# SparkFun_MOSFET_Power_Control_Kit.net
KiCad netlist of a schematic drawn in EAGLE
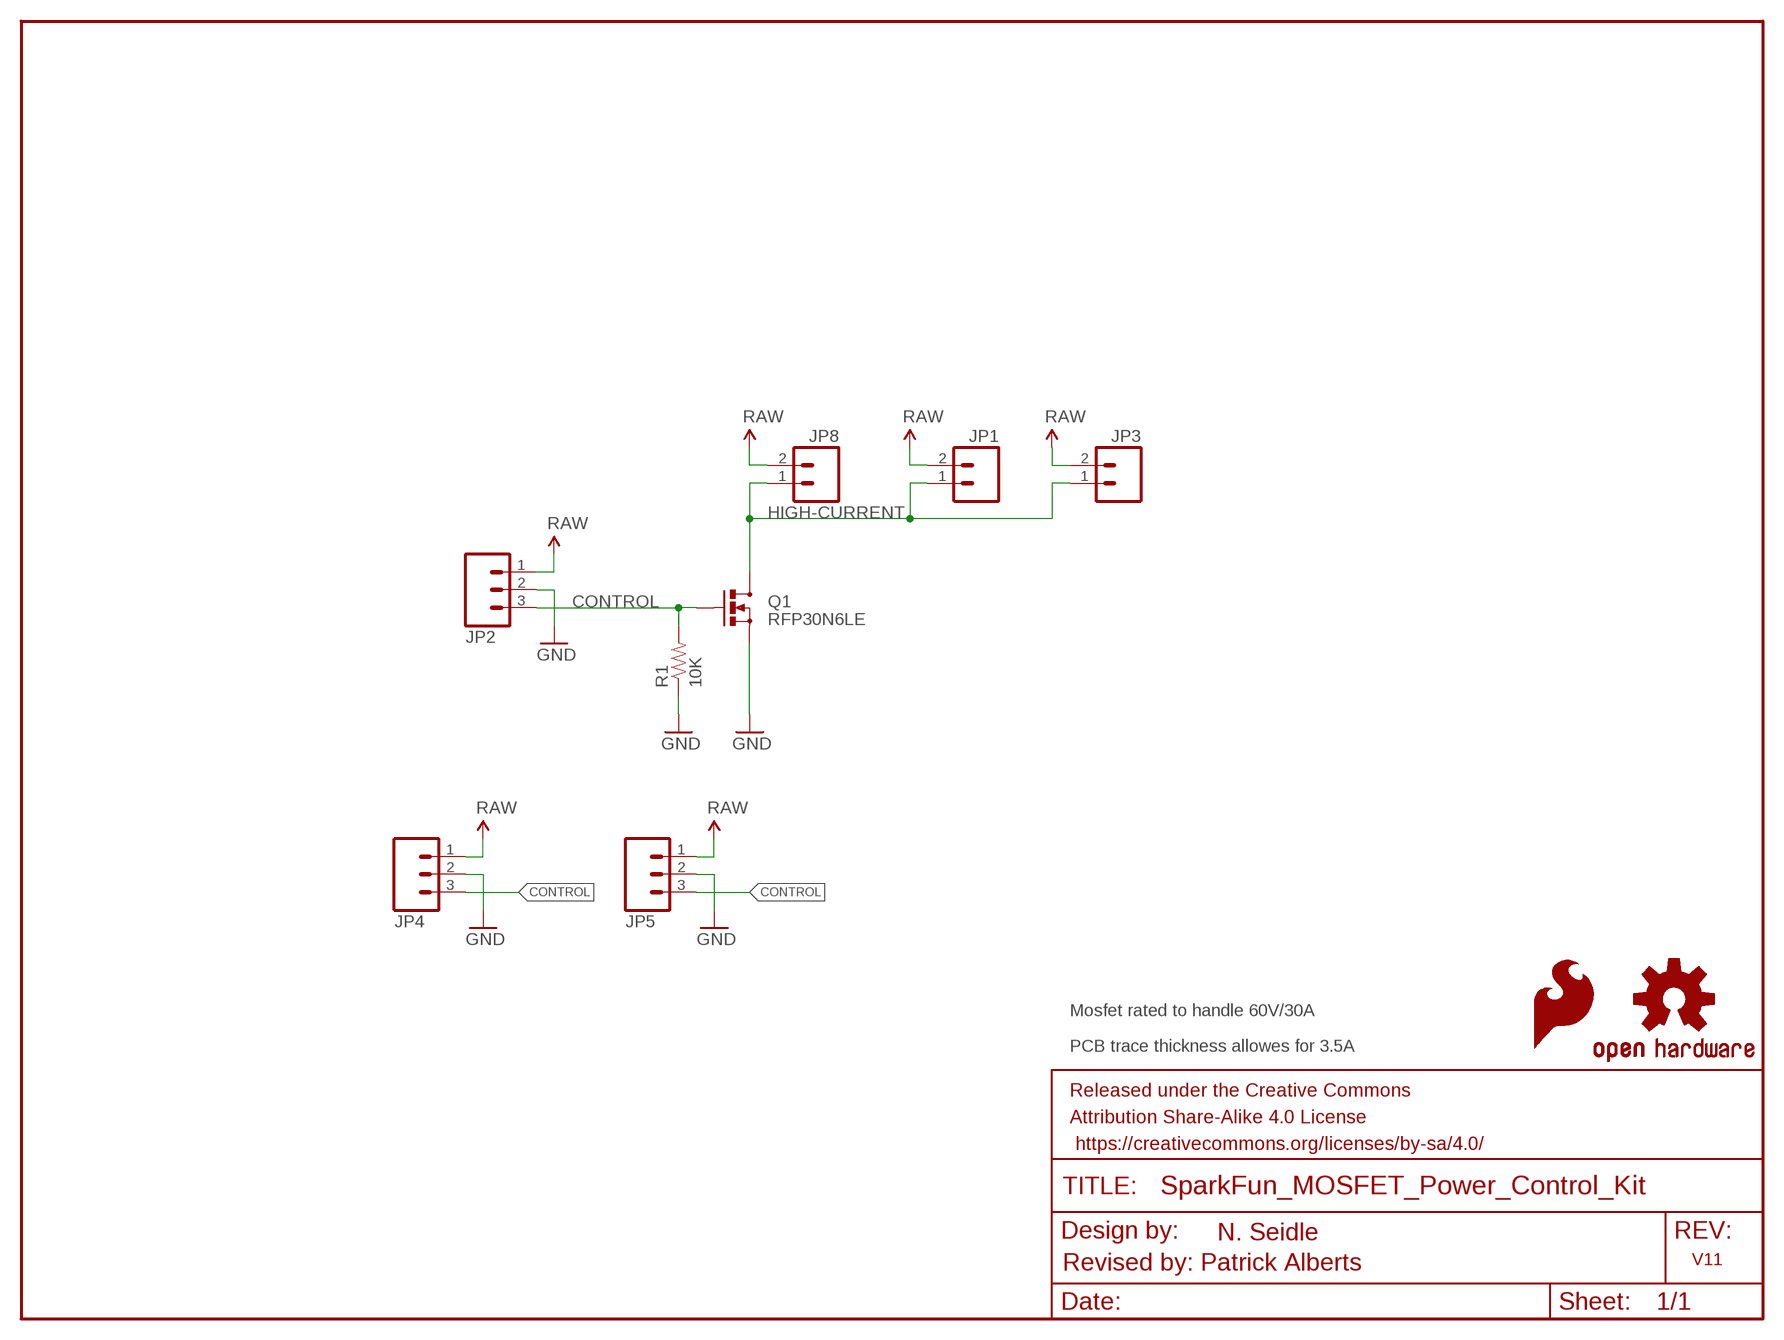
[diagram p0: schematic, sheet 1]

(export (version "E")
  (design (tool "Eeschema 10.0.6"))
  (components
    (comp (ref "FRAME1")
      (value "FRAME-LETTER")
      (footprint "eagle-import:CREATIVE_COMMONS")
      (libsource (lib "eagle-import") (part "FRAME-LETTER"))
    )
    (comp (ref "JP1")
      (value "M023.5MM")
      (footprint "eagle-import:SCREWTERMINAL-3.5MM-2")
      (libsource (lib "eagle-import") (part "M023.5MM"))
    )
    (comp (ref "JP2")
      (value "M03JST-PTH")
      (footprint "eagle-import:JST-3-PTH")
      (libsource (lib "eagle-import") (part "M03JST-PTH"))
    )
    (comp (ref "JP3")
      (value "M02PTH")
      (footprint "eagle-import:1X02")
      (libsource (lib "eagle-import") (part "SparkFun-Connectors_M02PTH"))
    )
    (comp (ref "JP4")
      (value "M03SCREW")
      (footprint "eagle-import:SCREWTERMINAL-3.5MM-3")
      (libsource (lib "eagle-import") (part "M03SCREW"))
    )
    (comp (ref "JP5")
      (value "M03PTH")
      (footprint "eagle-import:1X03")
      (libsource (lib "eagle-import") (part "M03PTH"))
    )
    (comp (ref "JP8")
      (value "M02JST-PTH-2")
      (footprint "eagle-import:JST-2-PTH")
      (libsource (lib "eagle-import") (part "M02JST-PTH-2"))
    )
    (comp (ref "LOGO1")
      (value "OSHW-LOGOS")
      (footprint "eagle-import:OSHW-LOGO-S")
      (libsource (lib "eagle-import") (part "OSHW-LOGOS"))
    )
    (comp (ref "LOGO2")
      (value "SFE_LOGO_FLAME.1_INCH")
      (footprint "eagle-import:SFE_LOGO_FLAME_.1")
      (libsource (lib "eagle-import") (part "SFE_LOGO_FLAME.1_INCH"))
    )
    (comp (ref "Q1")
      (value "RFP30N6LE")
      (footprint "eagle-import:TO220V")
      (libsource (lib "eagle-import") (part "MOSFET-NCHANNELPTH2"))
    )
    (comp (ref "R1")
      (value "10K")
      (footprint "eagle-import:AXIAL-0.3")
      (libsource (lib "eagle-import") (part "RESISTORPTH1"))
    )
  )
  (nets
    (net (code "1") (name "/HIGH-CURRENT") (class "Default")
      (node (ref "JP1") (pin "1") (pinfunction "1_1") (pintype "passive"))
      (node (ref "JP3") (pin "1") (pinfunction "1_1") (pintype "passive"))
      (node (ref "JP8") (pin "1") (pinfunction "1_1") (pintype "passive"))
      (node (ref "Q1") (pin "2") (pinfunction "D_2") (pintype "passive"))
    )
    (net (code "2") (name "CONTROL") (class "Default")
      (node (ref "JP2") (pin "3") (pinfunction "3_3") (pintype "passive"))
      (node (ref "JP4") (pin "3") (pinfunction "3_3") (pintype "passive"))
      (node (ref "JP5") (pin "3") (pinfunction "3_3") (pintype "passive"))
      (node (ref "Q1") (pin "1") (pinfunction "G_1") (pintype "passive"))
      (node (ref "R1") (pin "P$2") (pinfunction "2_P$2") (pintype "passive"))
    )
    (net (code "3") (name "GND") (class "Default")
      (node (ref "JP2") (pin "2") (pinfunction "2_2") (pintype "passive"))
      (node (ref "JP4") (pin "2") (pinfunction "2_2") (pintype "passive"))
      (node (ref "JP5") (pin "2") (pinfunction "2_2") (pintype "passive"))
      (node (ref "Q1") (pin "3") (pinfunction "S_3") (pintype "passive"))
      (node (ref "R1") (pin "P$1") (pinfunction "1_P$1") (pintype "passive"))
    )
    (net (code "4") (name "RAW") (class "Default")
      (node (ref "JP1") (pin "2") (pinfunction "2_2") (pintype "passive"))
      (node (ref "JP2") (pin "1") (pinfunction "1_1") (pintype "passive"))
      (node (ref "JP3") (pin "2") (pinfunction "2_2") (pintype "passive"))
      (node (ref "JP4") (pin "1") (pinfunction "1_1") (pintype "passive"))
      (node (ref "JP5") (pin "1") (pinfunction "1_1") (pintype "passive"))
      (node (ref "JP8") (pin "2") (pinfunction "2_2") (pintype "passive"))
    )
  )
)
